# Camera-V1_0.net
KiCad netlist of a schematic drawn in Altium Designer
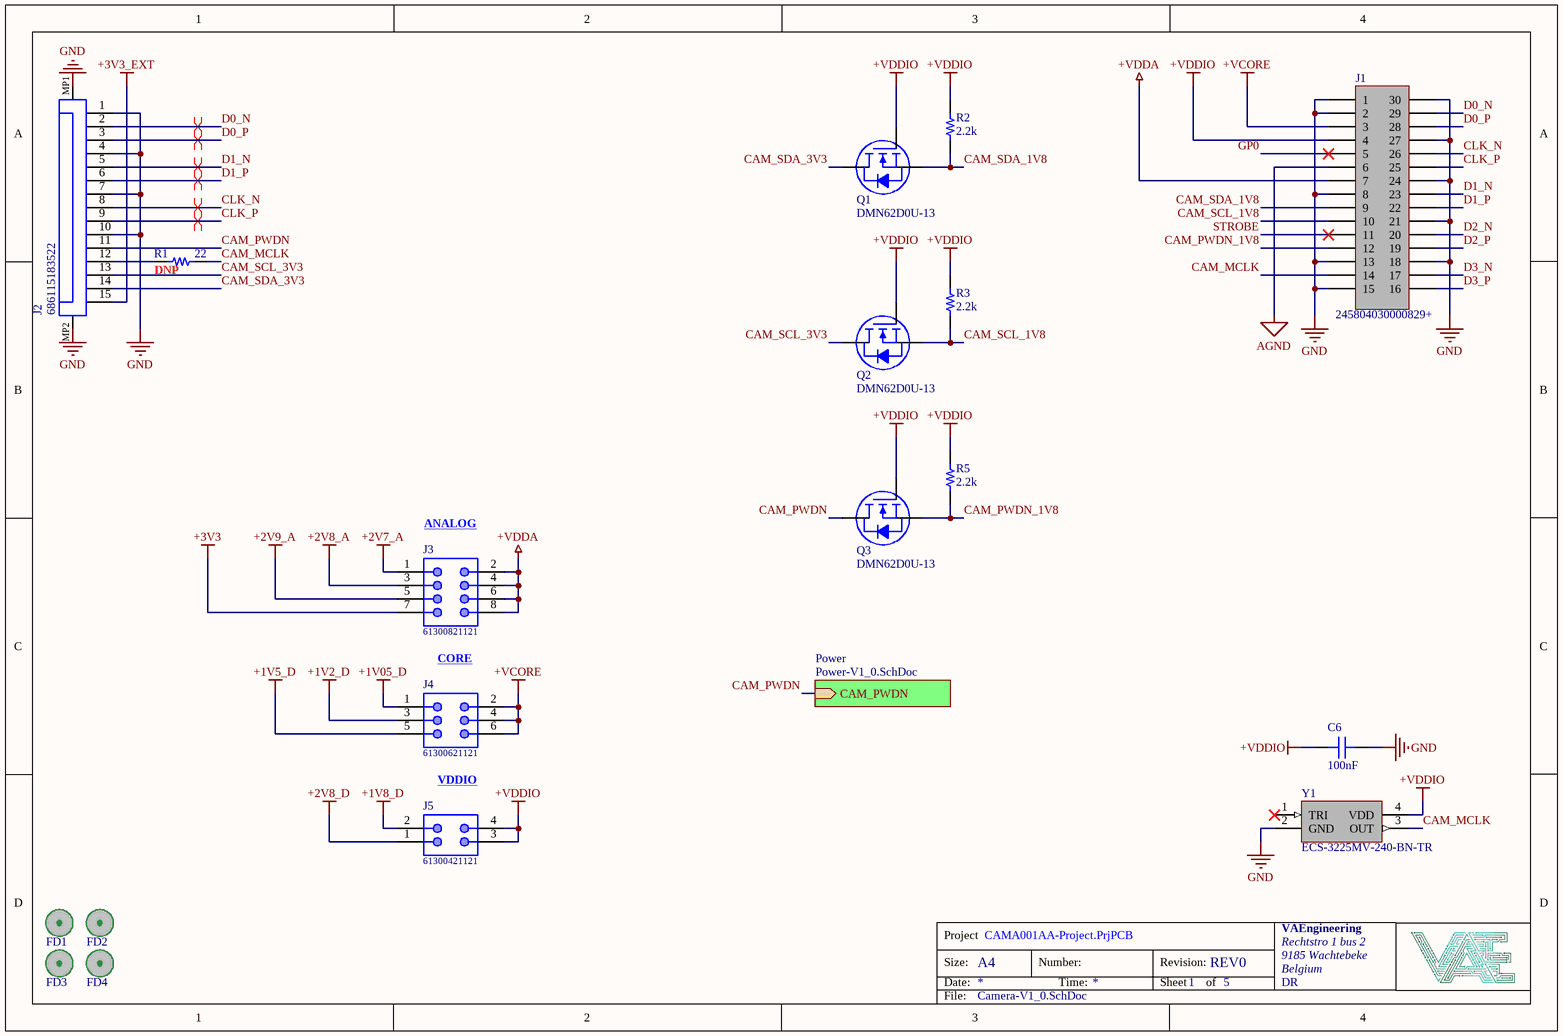
[diagram p0: Camera-V1_0.SchDoc]

(export (version "E")
  (design (tool "Eeschema 10.0.6"))
  (components
    (comp (ref "C6")
      (value "CL10B104KB8NNNL")
      (footprint "Esmart C0603")
      (description "CL10 Series 0603 0.1 uF 50 V ±10% Tolerance X7R Multilayer Ceramic Capacitor")
      (fields
        (field (name "MANUFACTURER") "Samsung")
        (field (name "TOLERANCE") "10%")
        (field (name "CAPACITANCE") "100nF")
      )
      (libsource (lib "Passives") (part "Samsung CL10B104KB8NNNL"))
    )
    (comp (ref "FD1")
      (value "Fiducial")
      (footprint "Fiducial 1")
      (fields (field (name "MANUFACTURER") "/"))
      (libsource (lib "Mechanical") (part "Fiducial"))
    )
    (comp (ref "FD2")
      (value "Fiducial")
      (footprint "Fiducial 1")
      (fields (field (name "MANUFACTURER") "/"))
      (libsource (lib "Mechanical") (part "Fiducial"))
    )
    (comp (ref "FD3")
      (value "Fiducial")
      (footprint "Fiducial 1")
      (fields (field (name "MANUFACTURER") "/"))
      (libsource (lib "Mechanical") (part "Fiducial"))
    )
    (comp (ref "FD4")
      (value "Fiducial")
      (footprint "Fiducial 1")
      (fields (field (name "MANUFACTURER") "/"))
      (libsource (lib "Mechanical") (part "Fiducial"))
    )
    (comp (ref "J1")
      (value "245804030000829+")
      (footprint "AVX 245804030000829+ - IMX477 - Reverse")
      (description "30 Position .04 mm Pitch Microleaf Mezzanine Connector")
      (fields (field (name "MANUFACTURER") "Kyocera AVX"))
      (libsource (lib "Connectors") (part "AVX 245804030000829+"))
    )
    (comp (ref "J2")
      (value "686115183522")
      (footprint "WURTH 686115183522")
      (description "WR-FPC SMT ZIF Horizontal Bottom Contact Low Profile, pitch 1mm, 15p")
      (fields (field (name "MANUFACTURER") "Wurth Elektronik"))
      (libsource (lib "Connectors") (part "Wurth 686115183522"))
    )
    (comp (ref "J3")
      (value "61300821121")
      (footprint "Wurth 61300821121")
      (description "WR-PHD Pin Header, THT, pitch 2.54mm, Dual Row, Vertical, 8pin")
      (fields (field (name "MANUFACTURER") "Wurth Electronics") (field (name "PUBLISHER") "Wurth Elektronik"))
      (libsource (lib "Connectors") (part "Wurth 61300821121"))
    )
    (comp (ref "J4")
      (value "61300621121")
      (footprint "Wurth 61300621121")
      (fields (field (name "MANUFACTURER") "Wurth Electronics") (field (name "PUBLISHER") "Wurth Elektronik"))
      (libsource (lib "Connectors") (part "Wurth 61300621121"))
    )
    (comp (ref "J5")
      (value "61300421121")
      (footprint "Wurth 61300421121")
      (description "THT Vertical Pin Header WR-PHD, Pitch 2.54 mm, Dual Row, 4 pins")
      (fields (field (name "MANUFACTURER") "Wurth Electronics") (field (name "PUBLISHER") "Wurth Elektronik"))
      (libsource (lib "Connectors") (part "Wurth 61300421121"))
    )
    (comp (ref "Q1")
      (value "DMN62D0U-13")
      (footprint "Diodes SOT23 MOSFET")
      (description "Trans MOSFET N-CH 60V 0.38A Automotive 3-Pin SOT-23 T/R")
      (fields (field (name "MANUFACTURER") "Diodes"))
      (libsource (lib "N-CH FETs") (part "Diodes DMN62D0U-13"))
    )
    (comp (ref "Q2")
      (value "DMN62D0U-13")
      (footprint "Diodes SOT23 MOSFET")
      (description "Trans MOSFET N-CH 60V 0.38A Automotive 3-Pin SOT-23 T/R")
      (fields (field (name "MANUFACTURER") "Diodes"))
      (libsource (lib "N-CH FETs") (part "Diodes DMN62D0U-13"))
    )
    (comp (ref "Q3")
      (value "DMN62D0U-13")
      (footprint "Diodes SOT23 MOSFET")
      (description "Trans MOSFET N-CH 60V 0.38A Automotive 3-Pin SOT-23 T/R")
      (fields (field (name "MANUFACTURER") "Diodes"))
      (libsource (lib "N-CH FETs") (part "Diodes DMN62D0U-13"))
    )
    (comp (ref "R1")
      (value "RMCF0603JT22R0")
      (footprint "ESmart R0603")
      (description "RES 22 OHM 5% 1/10W 0603")
      (fields
        (field (name "MANUFACTURER") "Stackpole Electronics")
        (field (name "TOLERANCE") "5%")
        (field (name "RESISTANCE") "22")
      )
      (libsource (lib "Passives") (part "Stackpole RMCF0603JT22R0"))
    )
    (comp (ref "R2")
      (value "RMCF0603FT2K20")
      (footprint "ESmart R0603")
      (description "RES 2.2K OHM 1% 1/10W 0603")
      (fields
        (field (name "MANUFACTURER") "Stackpole Electronics")
        (field (name "TOLERANCE") "1%")
        (field (name "RESISTANCE") "2.2k")
      )
      (libsource (lib "Passives") (part "Stackpole RMCF0603FT2K20"))
    )
    (comp (ref "R3")
      (value "RMCF0603FT2K20")
      (footprint "ESmart R0603")
      (description "RES 2.2K OHM 1% 1/10W 0603")
      (fields
        (field (name "MANUFACTURER") "Stackpole Electronics")
        (field (name "TOLERANCE") "1%")
        (field (name "RESISTANCE") "2.2k")
      )
      (libsource (lib "Passives") (part "Stackpole RMCF0603FT2K20"))
    )
    (comp (ref "R5")
      (value "RMCF0603FT2K20")
      (footprint "ESmart R0603")
      (description "RES 2.2K OHM 1% 1/10W 0603")
      (fields
        (field (name "MANUFACTURER") "Stackpole Electronics")
        (field (name "TOLERANCE") "1%")
        (field (name "RESISTANCE") "2.2k")
      )
      (libsource (lib "Passives") (part "Stackpole RMCF0603FT2K20"))
    )
    (comp (ref "Y1")
      (value "ECS-3225MV-240-BN-TR")
      (footprint "ECS ECS-3225MV")
      (description "Oscillator XO 24MHz ±50ppm 15pF HCMOS 55% 1.8V/2.5V/3.3V 4-Pin Mini-CSMD T/R")
      (fields (field (name "MANUFACTURER") "ECS International"))
      (libsource (lib "Crystals") (part "ECS-3225MV-240-BN-TR"))
    )
  )
  (nets
    (net (code "1") (name "+1V2_D") (class "Default")
      (node (ref "J4") (pin "3") (pinfunction "3_3") (pintype "passive"))
    )
    (net (code "2") (name "+1V05_D") (class "Default")
      (node (ref "J4") (pin "1") (pinfunction "1_1") (pintype "passive"))
    )
    (net (code "3") (name "+1V5_D") (class "Default")
      (node (ref "J4") (pin "5") (pinfunction "5_5") (pintype "passive"))
    )
    (net (code "4") (name "+1V8_D") (class "Default")
      (node (ref "J5") (pin "2") (pinfunction "2_2") (pintype "passive"))
    )
    (net (code "5") (name "+2V7_A") (class "Default")
      (node (ref "J3") (pin "1") (pinfunction "1_1") (pintype "passive"))
    )
    (net (code "6") (name "+2V8_A") (class "Default")
      (node (ref "J3") (pin "3") (pinfunction "3_3") (pintype "passive"))
    )
    (net (code "7") (name "+2V8_D") (class "Default")
      (node (ref "J5") (pin "1") (pinfunction "1_1") (pintype "passive"))
    )
    (net (code "8") (name "+2V9_A") (class "Default")
      (node (ref "J3") (pin "5") (pinfunction "5_5") (pintype "passive"))
    )
    (net (code "9") (name "+3V3") (class "Default")
      (node (ref "J3") (pin "7") (pinfunction "7_7") (pintype "passive"))
    )
    (net (code "10") (name "+3V3_EXT") (class "Default")
      (node (ref "J2") (pin "15") (pinfunction "15_15") (pintype "passive"))
    )
    (net (code "11") (name "+VCORE") (class "Default")
      (node (ref "J1") (pin "3") (pinfunction "3_3") (pintype "passive"))
      (node (ref "J4") (pin "2") (pinfunction "2_2") (pintype "passive"))
      (node (ref "J4") (pin "4") (pinfunction "4_4") (pintype "passive"))
      (node (ref "J4") (pin "6") (pinfunction "6_6") (pintype "passive"))
    )
    (net (code "12") (name "+VDDA") (class "Default")
      (node (ref "J1") (pin "7") (pinfunction "7_7") (pintype "passive"))
      (node (ref "J3") (pin "2") (pinfunction "2_2") (pintype "passive"))
      (node (ref "J3") (pin "4") (pinfunction "4_4") (pintype "passive"))
      (node (ref "J3") (pin "6") (pinfunction "6_6") (pintype "passive"))
      (node (ref "J3") (pin "8") (pinfunction "8_8") (pintype "passive"))
    )
    (net (code "13") (name "+VDDIO") (class "Default")
      (node (ref "C6") (pin "2") (pinfunction "2_2") (pintype "passive"))
      (node (ref "J1") (pin "4") (pinfunction "4_4") (pintype "passive"))
      (node (ref "J5") (pin "3") (pinfunction "3_3") (pintype "passive"))
      (node (ref "J5") (pin "4") (pinfunction "4_4") (pintype "passive"))
      (node (ref "Q1") (pin "G") (pinfunction "G_G") (pintype "passive"))
      (node (ref "Q2") (pin "G") (pinfunction "G_G") (pintype "passive"))
      (node (ref "Q3") (pin "G") (pinfunction "G_G") (pintype "passive"))
      (node (ref "R2") (pin "2") (pinfunction "2_2") (pintype "passive"))
      (node (ref "R3") (pin "2") (pinfunction "2_2") (pintype "passive"))
      (node (ref "R5") (pin "2") (pinfunction "2_2") (pintype "passive"))
      (node (ref "Y1") (pin "4") (pinfunction "VDD_4") (pintype "power_in"))
    )
    (net (code "14") (name "/CAM_MCLK") (class "Default")
      (node (ref "J1") (pin "14") (pinfunction "14_14") (pintype "passive"))
      (node (ref "R1") (pin "2") (pinfunction "2_2") (pintype "passive"))
      (node (ref "Y1") (pin "3") (pinfunction "OUT_3") (pintype "output"))
    )
    (net (code "15") (name "/CAM_PWDN") (class "Default")
      (node (ref "J2") (pin "11") (pinfunction "11_11") (pintype "passive"))
      (node (ref "Q3") (pin "D") (pinfunction "D_D") (pintype "passive"))
    )
    (net (code "16") (name "/CAM_PWDN_1V8") (class "Default")
      (node (ref "J1") (pin "12") (pinfunction "12_12") (pintype "passive"))
      (node (ref "Q3") (pin "S") (pinfunction "S_S") (pintype "passive"))
      (node (ref "R5") (pin "1") (pinfunction "1_1") (pintype "passive"))
    )
    (net (code "17") (name "/CAM_SCL_1V8") (class "Default")
      (node (ref "J1") (pin "10") (pinfunction "10_10") (pintype "passive"))
      (node (ref "Q2") (pin "S") (pinfunction "S_S") (pintype "passive"))
      (node (ref "R3") (pin "1") (pinfunction "1_1") (pintype "passive"))
    )
    (net (code "18") (name "/CAM_SCL_3V3") (class "Default")
      (node (ref "J2") (pin "13") (pinfunction "13_13") (pintype "passive"))
      (node (ref "Q2") (pin "D") (pinfunction "D_D") (pintype "passive"))
    )
    (net (code "19") (name "/CAM_SDA_1V8") (class "Default")
      (node (ref "J1") (pin "9") (pinfunction "9_9") (pintype "passive"))
      (node (ref "Q1") (pin "S") (pinfunction "S_S") (pintype "passive"))
      (node (ref "R2") (pin "1") (pinfunction "1_1") (pintype "passive"))
    )
    (net (code "20") (name "/CAM_SDA_3V3") (class "Default")
      (node (ref "J2") (pin "14") (pinfunction "14_14") (pintype "passive"))
      (node (ref "Q1") (pin "D") (pinfunction "D_D") (pintype "passive"))
    )
    (net (code "21") (name "/CLK_N") (class "Default")
      (node (ref "J1") (pin "26") (pinfunction "26_26") (pintype "passive"))
      (node (ref "J2") (pin "8") (pinfunction "8_8") (pintype "passive"))
    )
    (net (code "22") (name "/CLK_P") (class "Default")
      (node (ref "J1") (pin "25") (pinfunction "25_25") (pintype "passive"))
      (node (ref "J2") (pin "9") (pinfunction "9_9") (pintype "passive"))
    )
    (net (code "23") (name "/D0_N") (class "Default")
      (node (ref "J1") (pin "29") (pinfunction "29_29") (pintype "passive"))
      (node (ref "J2") (pin "2") (pinfunction "2_2") (pintype "passive"))
    )
    (net (code "24") (name "/D0_P") (class "Default")
      (node (ref "J1") (pin "28") (pinfunction "28_28") (pintype "passive"))
      (node (ref "J2") (pin "3") (pinfunction "3_3") (pintype "passive"))
    )
    (net (code "25") (name "/D1_N") (class "Default")
      (node (ref "J1") (pin "23") (pinfunction "23_23") (pintype "passive"))
      (node (ref "J2") (pin "5") (pinfunction "5_5") (pintype "passive"))
    )
    (net (code "26") (name "/D1_P") (class "Default")
      (node (ref "J1") (pin "22") (pinfunction "22_22") (pintype "passive"))
      (node (ref "J2") (pin "6") (pinfunction "6_6") (pintype "passive"))
    )
    (net (code "27") (name "/D2_N") (class "Default")
      (node (ref "J1") (pin "20") (pinfunction "20_20") (pintype "passive"))
    )
    (net (code "28") (name "/D2_P") (class "Default")
      (node (ref "J1") (pin "19") (pinfunction "19_19") (pintype "passive"))
    )
    (net (code "29") (name "/D3_N") (class "Default")
      (node (ref "J1") (pin "17") (pinfunction "17_17") (pintype "passive"))
    )
    (net (code "30") (name "/D3_P") (class "Default")
      (node (ref "J1") (pin "16") (pinfunction "16_16") (pintype "passive"))
    )
    (net (code "31") (name "/GP0") (class "Default")
      (node (ref "J1") (pin "5") (pinfunction "5_5") (pintype "passive+no_connect"))
    )
    (net (code "32") (name "/STROBE") (class "Default")
      (node (ref "J1") (pin "11") (pinfunction "11_11") (pintype "passive+no_connect"))
    )
    (net (code "33") (name "AGND") (class "Default")
      (node (ref "J1") (pin "6") (pinfunction "6_6") (pintype "passive"))
    )
    (net (code "34") (name "GND") (class "Default")
      (node (ref "C6") (pin "1") (pinfunction "1_1") (pintype "passive"))
      (node (ref "J1") (pin "1") (pinfunction "1_1") (pintype "passive"))
      (node (ref "J1") (pin "13") (pinfunction "13_13") (pintype "passive"))
      (node (ref "J1") (pin "15") (pinfunction "15_15") (pintype "passive"))
      (node (ref "J1") (pin "18") (pinfunction "18_18") (pintype "passive"))
      (node (ref "J1") (pin "2") (pinfunction "2_2") (pintype "passive"))
      (node (ref "J1") (pin "21") (pinfunction "21_21") (pintype "passive"))
      (node (ref "J1") (pin "24") (pinfunction "24_24") (pintype "passive"))
      (node (ref "J1") (pin "27") (pinfunction "27_27") (pintype "passive"))
      (node (ref "J1") (pin "30") (pinfunction "30_30") (pintype "passive"))
      (node (ref "J1") (pin "8") (pinfunction "8_8") (pintype "passive"))
      (node (ref "J2") (pin "1") (pinfunction "1_1") (pintype "passive"))
      (node (ref "J2") (pin "10") (pinfunction "10_10") (pintype "passive"))
      (node (ref "J2") (pin "4") (pinfunction "4_4") (pintype "passive"))
      (node (ref "J2") (pin "7") (pinfunction "7_7") (pintype "passive"))
      (node (ref "J2") (pin "MP1") (pinfunction "MP1_MP1") (pintype "passive"))
      (node (ref "J2") (pin "MP2") (pinfunction "MP2_MP2") (pintype "passive"))
      (node (ref "Y1") (pin "2") (pinfunction "GND_2") (pintype "power_in"))
    )
    (net (code "35") (name "Net-(J2-Pad12)") (class "Default")
      (node (ref "J2") (pin "12") (pinfunction "12_12") (pintype "passive"))
      (node (ref "R1") (pin "1") (pinfunction "1_1") (pintype "passive"))
    )
    (net (code "36") (name "unconnected-(Y1-TRI-Pad1)") (class "Default")
      (node (ref "Y1") (pin "1") (pinfunction "TRI_1") (pintype "input+no_connect"))
    )
  )
)
